# relay_and_contactor.net
KiCad netlist of a schematic drawn in Altium Designer
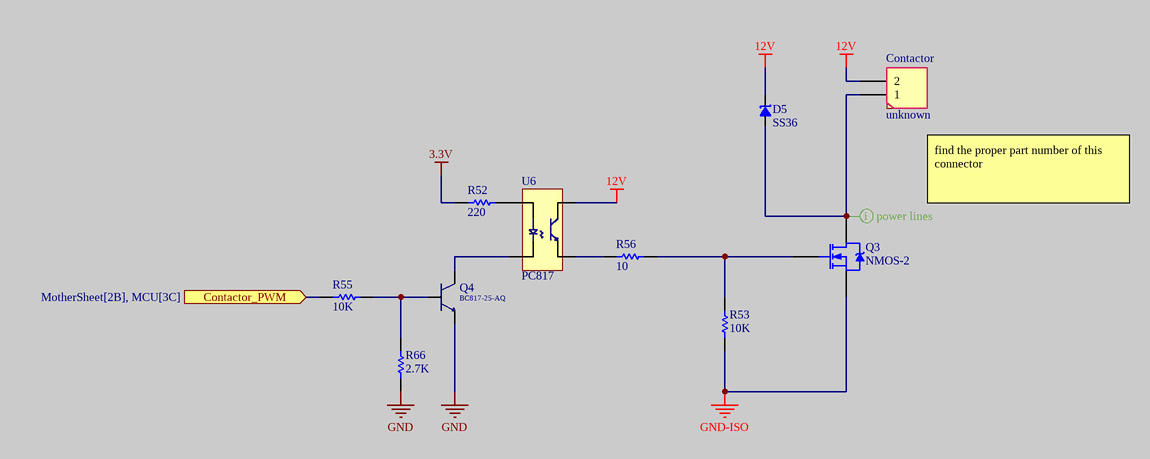
[diagram p0: relay and contactor.SchDoc]

(export (version "E")
  (design (tool "Eeschema 10.0.6"))
  (components
    (comp (ref "Contactor")
      (value "unknown")
      (footprint "LED-RIGHT")
      (description "Header, 2-Pin")
      (libsource (lib "eLIB") (part "Header1*2"))
    )
    (comp (ref "D5")
      (value "SS36")
      (footprint "SMA")
      (description "Fast Schottky Diode")
      (fields (field (name "PUBLISHER") "Altium Limited"))
      (libsource (lib "eLIB") (part "SS36"))
    )
    (comp (ref "Q3")
      (value "NMOS-2")
      (footprint "dpak")
      (description "N-Channel Power MOSFET")
      (fields (field (name "PUBLISHER") "Altium Limited"))
      (libsource (lib "eLIB") (part "NMOS-2"))
    )
    (comp (ref "Q4")
      (value "NPN transistor")
      (footprint "NPN")
      (description "45 V, 0.5 A")
      (fields (field (name "TRANSISTOR") "BC817-25-AQ"))
      (libsource (lib "eLIB") (part "BC817"))
    )
    (comp (ref "R52")
      (value "220")
      (footprint "RESC0603")
      (description "0603,0.1W")
      (fields (field (name "PUBLISHER") "Altium Limited"))
      (libsource (lib "eLIB") (part "Resistor"))
    )
    (comp (ref "R53")
      (value "10K")
      (footprint "RESC0603")
      (description "0603,0.1W")
      (fields (field (name "PUBLISHER") "Altium Limited"))
      (libsource (lib "eLIB") (part "Resistor"))
    )
    (comp (ref "R55")
      (value "10K")
      (footprint "RESC0603")
      (description "0603,0.1W")
      (fields (field (name "PUBLISHER") "Altium Limited"))
      (libsource (lib "eLIB") (part "Resistor"))
    )
    (comp (ref "R56")
      (value "10")
      (footprint "RESC0603")
      (description "0603,0.1W")
      (fields (field (name "PUBLISHER") "Altium Limited"))
      (libsource (lib "eLIB") (part "Resistor"))
    )
    (comp (ref "R66")
      (value "2.7K")
      (footprint "RESC0603")
      (description "0603,0.1W")
      (fields (field (name "PUBLISHER") "Altium Limited"))
      (libsource (lib "eLIB") (part "Resistor"))
    )
    (comp (ref "U6")
      (value "PC817")
      (footprint "PC817")
      (description "PC817 optocoupler")
      (libsource (lib "eLIB") (part "PC817"))
    )
  )
  (nets
    (net (code "1") (name "/Contactor_PWM") (class "Default")
      (node (ref "R55") (pin "2") (pinfunction "2_2") (pintype "passive"))
    )
    (net (code "2") (name "3.3V") (class "Default")
      (node (ref "R52") (pin "2") (pinfunction "2_2") (pintype "passive"))
    )
    (net (code "3") (name "12V") (class "Default")
      (node (ref "Contactor") (pin "2") (pinfunction "2_2") (pintype "passive"))
      (node (ref "D5") (pin "2") (pinfunction "K_2") (pintype "passive"))
      (node (ref "U6") (pin "4") (pinfunction "4_4") (pintype "passive"))
    )
    (net (code "4") (name "GND") (class "Default")
      (node (ref "Q4") (pin "2") (pinfunction "E_2") (pintype "passive"))
      (node (ref "R66") (pin "2") (pinfunction "2_2") (pintype "passive"))
    )
    (net (code "5") (name "GND-ISO") (class "Default")
      (node (ref "Q3") (pin "3") (pinfunction "S_3") (pintype "passive"))
      (node (ref "R53") (pin "1") (pinfunction "1_1") (pintype "passive"))
    )
    (net (code "6") (name "Net-(D5-A)") (class "Default")
      (node (ref "Contactor") (pin "1") (pinfunction "1_1") (pintype "passive"))
      (node (ref "D5") (pin "1") (pinfunction "A_1") (pintype "passive"))
      (node (ref "Q3") (pin "2") (pinfunction "D_2") (pintype "passive"))
    )
    (net (code "7") (name "Net-(Q3-G)") (class "Default")
      (node (ref "Q3") (pin "1") (pinfunction "G_1") (pintype "passive"))
      (node (ref "R53") (pin "2") (pinfunction "2_2") (pintype "passive"))
      (node (ref "R56") (pin "1") (pinfunction "1_1") (pintype "passive"))
    )
    (net (code "8") (name "Net-(Q4-B)") (class "Default")
      (node (ref "Q4") (pin "1") (pinfunction "B_1") (pintype "passive"))
      (node (ref "R55") (pin "1") (pinfunction "1_1") (pintype "passive"))
      (node (ref "R66") (pin "1") (pinfunction "1_1") (pintype "passive"))
    )
    (net (code "9") (name "Net-(Q4-C)") (class "Default")
      (node (ref "Q4") (pin "3") (pinfunction "C_3") (pintype "passive"))
      (node (ref "U6") (pin "2") (pinfunction "2_2") (pintype "passive"))
    )
    (net (code "10") (name "Net-(R52-Pad1)") (class "Default")
      (node (ref "R52") (pin "1") (pinfunction "1_1") (pintype "passive"))
      (node (ref "U6") (pin "1") (pinfunction "1_1") (pintype "passive"))
    )
    (net (code "11") (name "Net-(R56-Pad2)") (class "Default")
      (node (ref "R56") (pin "2") (pinfunction "2_2") (pintype "passive"))
      (node (ref "U6") (pin "3") (pinfunction "3_3") (pintype "passive"))
    )
  )
)
